# schematic.net
KiCad netlist of a schematic drawn in EAGLE
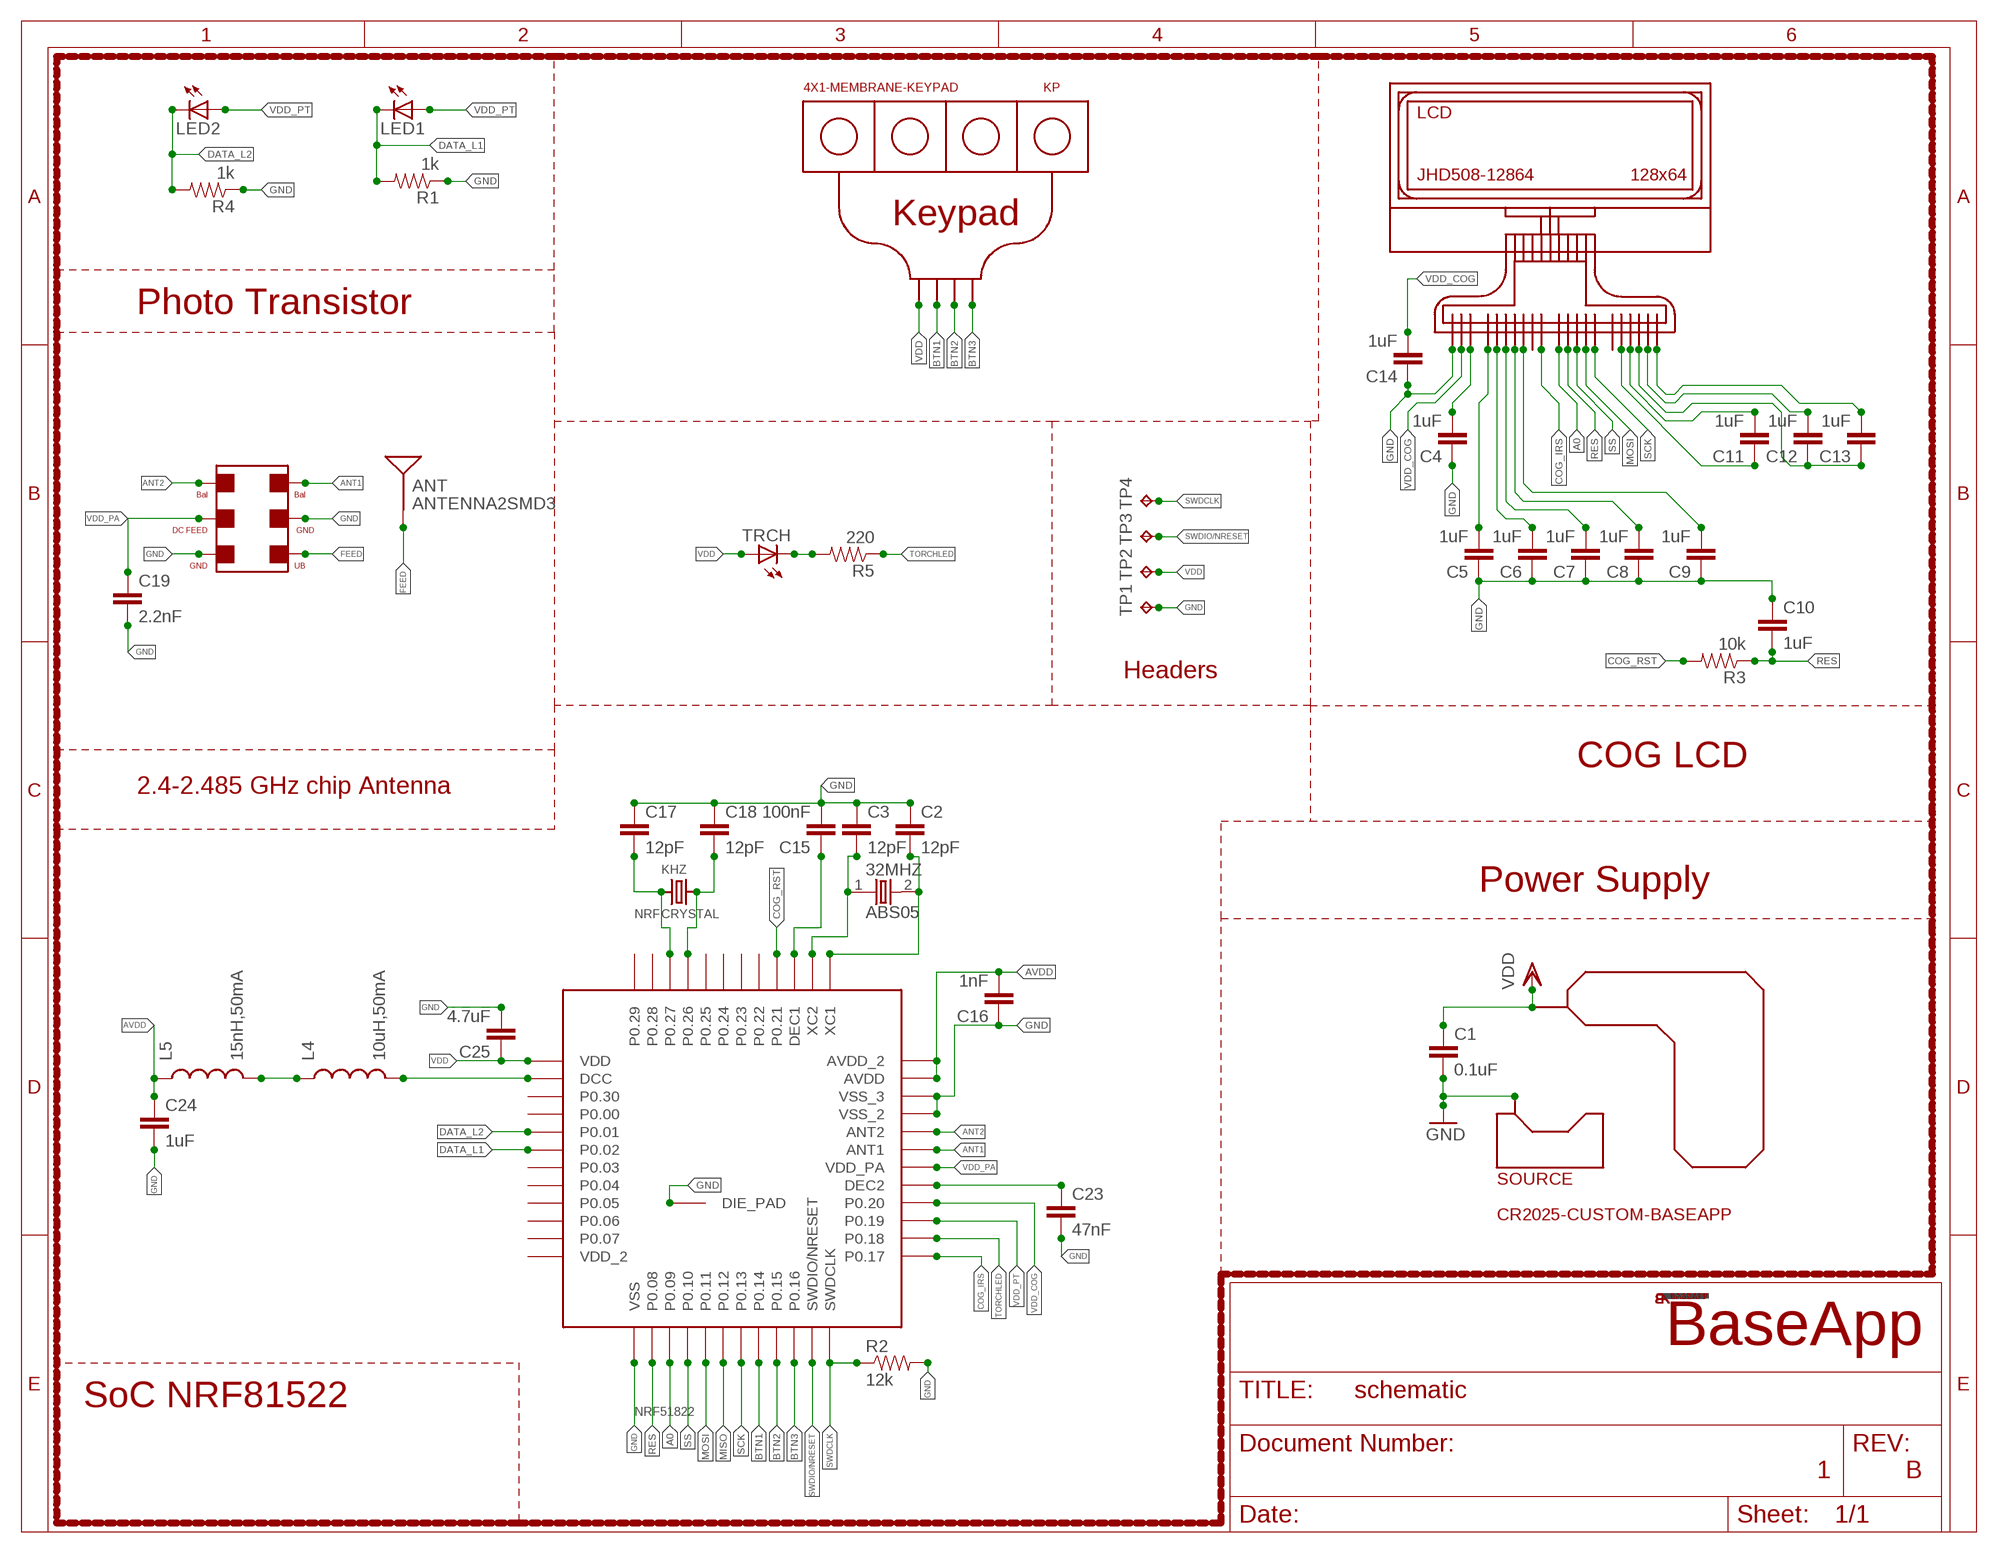
[diagram p0: schematic, sheet 1]

(export (version "E")
  (design (tool "Eeschema 10.0.6"))
  (components
    (comp (ref "32MHZ")
      (value "ABS05")
      (footprint "eagle-import:ABS05")
      (libsource (lib "eagle-import") (part "ABS05"))
    )
    (comp (ref "ANT")
      (value "ANTENNA2SMD3")
      (footprint "eagle-import:ANTENNA-CHIP4")
      (libsource (lib "eagle-import") (part "ANTENNA2SMD3"))
    )
    (comp (ref "BU")
      (value "2450BM14E0003_BALUN")
      (footprint "eagle-import:6PCPADS")
      (libsource (lib "eagle-import") (part "2450BM14E0003_BALUN"))
    )
    (comp (ref "C1")
      (value "0.1uF")
      (footprint "eagle-import:0402-CAP")
      (libsource (lib "eagle-import") (part "CAP0402-CAP"))
    )
    (comp (ref "C2")
      (value "12pF")
      (footprint "eagle-import:0402-CAP")
      (libsource (lib "eagle-import") (part "CAP0402-CAP"))
    )
    (comp (ref "C3")
      (value "12pF")
      (footprint "eagle-import:0402-CAP")
      (libsource (lib "eagle-import") (part "CAP0402-CAP"))
    )
    (comp (ref "C4")
      (value "1uF")
      (footprint "eagle-import:0402-CAP")
      (libsource (lib "eagle-import") (part "CAP0402-CAP"))
    )
    (comp (ref "C5")
      (value "1uF")
      (footprint "eagle-import:0402-CAP")
      (libsource (lib "eagle-import") (part "CAP0402-CAP"))
    )
    (comp (ref "C6")
      (value "1uF")
      (footprint "eagle-import:0402-CAP")
      (libsource (lib "eagle-import") (part "CAP0402-CAP"))
    )
    (comp (ref "C7")
      (value "1uF")
      (footprint "eagle-import:0402-CAP")
      (libsource (lib "eagle-import") (part "CAP0402-CAP"))
    )
    (comp (ref "C8")
      (value "1uF")
      (footprint "eagle-import:0402-CAP")
      (libsource (lib "eagle-import") (part "CAP0402-CAP"))
    )
    (comp (ref "C9")
      (value "1uF")
      (footprint "eagle-import:0402-CAP")
      (libsource (lib "eagle-import") (part "CAP0402-CAP"))
    )
    (comp (ref "C10")
      (value "1uF")
      (footprint "eagle-import:0402-CAP")
      (libsource (lib "eagle-import") (part "CAP0402-CAP"))
    )
    (comp (ref "C11")
      (value "1uF")
      (footprint "eagle-import:0402-CAP")
      (libsource (lib "eagle-import") (part "CAP0402-CAP"))
    )
    (comp (ref "C12")
      (value "1uF")
      (footprint "eagle-import:0402-CAP")
      (libsource (lib "eagle-import") (part "CAP0402-CAP"))
    )
    (comp (ref "C13")
      (value "1uF")
      (footprint "eagle-import:0402-CAP")
      (libsource (lib "eagle-import") (part "CAP0402-CAP"))
    )
    (comp (ref "C14")
      (value "1uF")
      (footprint "eagle-import:0402-CAP")
      (libsource (lib "eagle-import") (part "CAP0402-CAP"))
    )
    (comp (ref "C15")
      (value "100nF")
      (footprint "eagle-import:0402-CAP")
      (libsource (lib "eagle-import") (part "CAP0402-CAP"))
    )
    (comp (ref "C16")
      (value "1nF")
      (footprint "eagle-import:0402-CAP")
      (libsource (lib "eagle-import") (part "CAP0402-CAP"))
    )
    (comp (ref "C17")
      (value "12pF")
      (footprint "eagle-import:0402-CAP")
      (libsource (lib "eagle-import") (part "CAP0402-CAP"))
    )
    (comp (ref "C18")
      (value "12pF")
      (footprint "eagle-import:0402-CAP")
      (libsource (lib "eagle-import") (part "CAP0402-CAP"))
    )
    (comp (ref "C19")
      (value "2.2nF")
      (footprint "eagle-import:0402-CAP")
      (libsource (lib "eagle-import") (part "CAP0402-CAP"))
    )
    (comp (ref "C23")
      (value "47nF")
      (footprint "eagle-import:0402-CAP")
      (libsource (lib "eagle-import") (part "CAP0402-CAP"))
    )
    (comp (ref "C24")
      (value "1uF")
      (footprint "eagle-import:0402-CAP")
      (libsource (lib "eagle-import") (part "CAP0402-CAP"))
    )
    (comp (ref "C25")
      (value "4.7uF")
      (footprint "eagle-import:0402-CAP")
      (libsource (lib "eagle-import") (part "CAP0402-CAP"))
    )
    (comp (ref "KHZ")
      (value "CRYSTAL")
      (footprint "eagle-import:ABS05")
      (libsource (lib "eagle-import") (part "CRYSTAL"))
    )
    (comp (ref "KP")
      (value "4X1-MEMBRANE-KEYPAD")
      (footprint "eagle-import:4X1-MEMBRANE-KEYPAD")
      (libsource (lib "eagle-import") (part "4X1-MEMBRANE-KEYPAD"))
    )
    (comp (ref "L4")
      (value "10uH,50mA")
      (footprint "eagle-import:C0402")
      (libsource (lib "eagle-import") (part "INDUCTOR0402"))
    )
    (comp (ref "L5")
      (value "15nH,50mA")
      (footprint "eagle-import:C0402")
      (libsource (lib "eagle-import") (part "INDUCTOR0402"))
    )
    (comp (ref "LCD")
      (value "JHD508-12864")
      (footprint "eagle-import:FSTN")
      (libsource (lib "eagle-import") (part "JHD508-12864"))
    )
    (comp (ref "LED1")
      (value "LEDCHIP-LED0805")
      (footprint "eagle-import:CHIP-LED0805")
      (libsource (lib "eagle-import") (part "LEDCHIP-LED0805"))
    )
    (comp (ref "LED2")
      (value "LEDCHIP-LED0805")
      (footprint "eagle-import:CHIP-LED0805")
      (libsource (lib "eagle-import") (part "LEDCHIP-LED0805"))
    )
    (comp (ref "NRF")
      (value "NRF51822")
      (footprint "eagle-import:QFN48")
      (libsource (lib "eagle-import") (part "NRF51822"))
    )
    (comp (ref "R1")
      (value "1k")
      (footprint "eagle-import:0402-RES")
      (libsource (lib "eagle-import") (part "RESISTOR0402-RES"))
    )
    (comp (ref "R2")
      (value "12k")
      (footprint "eagle-import:0402-RES")
      (libsource (lib "eagle-import") (part "RESISTOR0402-RES"))
    )
    (comp (ref "R3")
      (value "10k")
      (footprint "eagle-import:0402-RES")
      (libsource (lib "eagle-import") (part "RESISTOR0402-RES"))
    )
    (comp (ref "R4")
      (value "1k")
      (footprint "eagle-import:0402-RES")
      (libsource (lib "eagle-import") (part "RESISTOR0402-RES"))
    )
    (comp (ref "R5")
      (value "220")
      (footprint "eagle-import:0402-RES")
      (libsource (lib "eagle-import") (part "RESISTOR0402-RES"))
    )
    (comp (ref "SOURCE")
      (value "CR2025-CUSTOM-BASEAPP")
      (footprint "eagle-import:CR2025-CUSTOM-BASEAPP")
      (libsource (lib "eagle-import") (part "CR2025-CUSTOM-BASEAPP"))
    )
    (comp (ref "TP1")
      (value "TPTP06SQ")
      (footprint "eagle-import:TP06SQ")
      (libsource (lib "eagle-import") (part "TPTP06SQ"))
    )
    (comp (ref "TP2")
      (value "TPTP06SQ")
      (footprint "eagle-import:TP06SQ")
      (libsource (lib "eagle-import") (part "TPTP06SQ"))
    )
    (comp (ref "TP3")
      (value "TPTP06SQ")
      (footprint "eagle-import:TP06SQ")
      (libsource (lib "eagle-import") (part "TPTP06SQ"))
    )
    (comp (ref "TP4")
      (value "TPTP06SQ")
      (footprint "eagle-import:TP06SQ")
      (libsource (lib "eagle-import") (part "TPTP06SQ"))
    )
    (comp (ref "TRCH")
      (value "LEDSML0603")
      (footprint "eagle-import:SML0603")
      (libsource (lib "eagle-import") (part "LEDSML0603"))
    )
  )
  (nets
    (net (code "1") (name "A0") (class "Default")
      (node (ref "LCD") (pin "P$19") (pinfunction "A0_P$19") (pintype "bidirectional"))
      (node (ref "NRF") (pin "15") (pinfunction "P0.09_15") (pintype "bidirectional"))
    )
    (net (code "2") (name "ANT1") (class "Default")
      (node (ref "BU") (pin "P$3") (pinfunction "3_P$3") (pintype "bidirectional"))
      (node (ref "NRF") (pin "31") (pinfunction "ANT1_31") (pintype "bidirectional"))
    )
    (net (code "3") (name "ANT2") (class "Default")
      (node (ref "BU") (pin "P$4") (pinfunction "4_P$4") (pintype "bidirectional"))
      (node (ref "NRF") (pin "32") (pinfunction "ANT2_32") (pintype "bidirectional"))
    )
    (net (code "4") (name "AVDD") (class "Default")
      (node (ref "C16") (pin "2") (pinfunction "2_2") (pintype "passive"))
      (node (ref "C24") (pin "1") (pinfunction "1_1") (pintype "passive"))
      (node (ref "L5") (pin "1") (pinfunction "1_1") (pintype "passive"))
      (node (ref "NRF") (pin "35") (pinfunction "AVDD_35") (pintype "bidirectional"))
      (node (ref "NRF") (pin "36") (pinfunction "AVDD_2_36") (pintype "bidirectional"))
    )
    (net (code "5") (name "BTN1") (class "Default")
      (node (ref "KP") (pin "P$2") (pinfunction "P$2_P$2") (pintype "bidirectional"))
      (node (ref "NRF") (pin "20") (pinfunction "P0.14_20") (pintype "bidirectional"))
    )
    (net (code "6") (name "BTN2") (class "Default")
      (node (ref "KP") (pin "P$3") (pinfunction "P$3_P$3") (pintype "bidirectional"))
      (node (ref "NRF") (pin "21") (pinfunction "P0.15_21") (pintype "bidirectional"))
    )
    (net (code "7") (name "BTN3") (class "Default")
      (node (ref "KP") (pin "P$4") (pinfunction "P$4_P$4") (pintype "bidirectional"))
      (node (ref "NRF") (pin "22") (pinfunction "P0.16_22") (pintype "bidirectional"))
    )
    (net (code "8") (name "COG_IRS") (class "Default")
      (node (ref "LCD") (pin "P$1") (pinfunction "IRS_P$1") (pintype "bidirectional"))
      (node (ref "NRF") (pin "25") (pinfunction "P0.17_25") (pintype "bidirectional"))
    )
    (net (code "9") (name "COG_RST") (class "Default")
      (node (ref "NRF") (pin "40") (pinfunction "P0.21_40") (pintype "bidirectional"))
      (node (ref "R3") (pin "2") (pinfunction "2_2") (pintype "passive"))
    )
    (net (code "10") (name "DATA_L1") (class "Default")
      (node (ref "LED1") (pin "C") (pinfunction "C_C") (pintype "passive"))
      (node (ref "NRF") (pin "6") (pinfunction "P0.02_6") (pintype "bidirectional"))
      (node (ref "R1") (pin "2") (pinfunction "2_2") (pintype "passive"))
    )
    (net (code "11") (name "DATA_L2") (class "Default")
      (node (ref "LED2") (pin "C") (pinfunction "C_C") (pintype "passive"))
      (node (ref "NRF") (pin "5") (pinfunction "P0.01_5") (pintype "bidirectional"))
      (node (ref "R4") (pin "2") (pinfunction "2_2") (pintype "passive"))
    )
    (net (code "12") (name "FEED") (class "Default")
      (node (ref "ANT") (pin "SIG") (pinfunction "SIGNAL_SIG") (pintype "bidirectional"))
      (node (ref "BU") (pin "P$1") (pinfunction "1_P$1") (pintype "bidirectional"))
    )
    (net (code "13") (name "GND") (class "Default")
      (node (ref "BU") (pin "P$2") (pinfunction "2_P$2") (pintype "bidirectional"))
      (node (ref "BU") (pin "P$6") (pinfunction "6_P$6") (pintype "bidirectional"))
      (node (ref "C1") (pin "2") (pinfunction "2_2") (pintype "passive"))
      (node (ref "C10") (pin "1") (pinfunction "1_1") (pintype "passive"))
      (node (ref "C14") (pin "1") (pinfunction "1_1") (pintype "passive"))
      (node (ref "C15") (pin "2") (pinfunction "2_2") (pintype "passive"))
      (node (ref "C16") (pin "1") (pinfunction "1_1") (pintype "passive"))
      (node (ref "C17") (pin "1") (pinfunction "1_1") (pintype "passive"))
      (node (ref "C18") (pin "1") (pinfunction "1_1") (pintype "passive"))
      (node (ref "C19") (pin "2") (pinfunction "2_2") (pintype "passive"))
      (node (ref "C2") (pin "1") (pinfunction "1_1") (pintype "passive"))
      (node (ref "C23") (pin "2") (pinfunction "2_2") (pintype "passive"))
      (node (ref "C24") (pin "2") (pinfunction "2_2") (pintype "passive"))
      (node (ref "C25") (pin "2") (pinfunction "2_2") (pintype "passive"))
      (node (ref "C3") (pin "1") (pinfunction "1_1") (pintype "passive"))
      (node (ref "C4") (pin "1") (pinfunction "1_1") (pintype "passive"))
      (node (ref "C5") (pin "1") (pinfunction "1_1") (pintype "passive"))
      (node (ref "C6") (pin "1") (pinfunction "1_1") (pintype "passive"))
      (node (ref "C7") (pin "1") (pinfunction "1_1") (pintype "passive"))
      (node (ref "C8") (pin "1") (pinfunction "1_1") (pintype "passive"))
      (node (ref "C9") (pin "1") (pinfunction "1_1") (pintype "passive"))
      (node (ref "LCD") (pin "P$15") (pinfunction "GND_P$15") (pintype "bidirectional"))
      (node (ref "NRF") (pin "13") (pinfunction "VSS_13") (pintype "bidirectional"))
      (node (ref "NRF") (pin "33") (pinfunction "VSS_2_33") (pintype "bidirectional"))
      (node (ref "NRF") (pin "34") (pinfunction "VSS_3_34") (pintype "bidirectional"))
      (node (ref "NRF") (pin "GND") (pinfunction "DIE_PAD_GND") (pintype "bidirectional"))
      (node (ref "R1") (pin "1") (pinfunction "1_1") (pintype "passive"))
      (node (ref "R2") (pin "2") (pinfunction "2_2") (pintype "passive"))
      (node (ref "R4") (pin "1") (pinfunction "1_1") (pintype "passive"))
      (node (ref "SOURCE") (pin "1") (pinfunction "GND_1") (pintype "bidirectional"))
      (node (ref "TP1") (pin "TP") (pinfunction "TP_TP") (pintype "input"))
    )
    (net (code "14") (name "MISO") (class "Default")
      (node (ref "NRF") (pin "18") (pinfunction "P0.12_18") (pintype "bidirectional"))
    )
    (net (code "15") (name "MOSI") (class "Default")
      (node (ref "LCD") (pin "P$17") (pinfunction "SI_P$17") (pintype "bidirectional"))
      (node (ref "NRF") (pin "17") (pinfunction "P0.11_17") (pintype "bidirectional"))
    )
    (net (code "16") (name "Net-(KHZ-1)") (class "Default")
      (node (ref "C17") (pin "2") (pinfunction "2_2") (pintype "passive"))
      (node (ref "KHZ") (pin "P$1") (pinfunction "1_P$1") (pintype "passive"))
      (node (ref "NRF") (pin "46") (pinfunction "P0.27_46") (pintype "bidirectional"))
    )
    (net (code "17") (name "Net-(KHZ-2)") (class "Default")
      (node (ref "C18") (pin "2") (pinfunction "2_2") (pintype "passive"))
      (node (ref "KHZ") (pin "P$2") (pinfunction "2_P$2") (pintype "passive"))
      (node (ref "NRF") (pin "45") (pinfunction "P0.26_45") (pintype "bidirectional"))
    )
    (net (code "18") (name "Net-(L4-Pad1)") (class "Default")
      (node (ref "L4") (pin "1") (pinfunction "1_1") (pintype "passive"))
      (node (ref "L5") (pin "2") (pinfunction "2_2") (pintype "passive"))
    )
    (net (code "19") (name "Net-(LCD-CAP1N)") (class "Default")
      (node (ref "C12") (pin "1") (pinfunction "1_1") (pintype "passive"))
      (node (ref "C13") (pin "1") (pinfunction "1_1") (pintype "passive"))
      (node (ref "LCD") (pin "P$11") (pinfunction "CAP1N_P$11") (pintype "bidirectional"))
    )
    (net (code "20") (name "Net-(LCD-CAP1P)") (class "Default")
      (node (ref "C12") (pin "2") (pinfunction "2_2") (pintype "passive"))
      (node (ref "LCD") (pin "P$12") (pinfunction "CAP1P_P$12") (pintype "bidirectional"))
    )
    (net (code "21") (name "Net-(LCD-CAP2N)") (class "Default")
      (node (ref "C11") (pin "2") (pinfunction "2_2") (pintype "passive"))
      (node (ref "LCD") (pin "P$10") (pinfunction "CAP2N_P$10") (pintype "bidirectional"))
    )
    (net (code "22") (name "Net-(LCD-CAP2P)") (class "Default")
      (node (ref "C11") (pin "1") (pinfunction "1_1") (pintype "passive"))
      (node (ref "LCD") (pin "P$9") (pinfunction "CAP2P_P$9") (pintype "bidirectional"))
    )
    (net (code "23") (name "Net-(LCD-CAP3N)") (class "Default")
      (node (ref "C13") (pin "2") (pinfunction "2_2") (pintype "passive"))
      (node (ref "LCD") (pin "P$13") (pinfunction "CAP3N_P$13") (pintype "bidirectional"))
    )
    (net (code "24") (name "Net-(LCD-V1)") (class "Default")
      (node (ref "C5") (pin "2") (pinfunction "2_2") (pintype "passive"))
      (node (ref "LCD") (pin "P$7") (pinfunction "V1_P$7") (pintype "bidirectional"))
    )
    (net (code "25") (name "Net-(LCD-V2)") (class "Default")
      (node (ref "C6") (pin "2") (pinfunction "2_2") (pintype "passive"))
      (node (ref "LCD") (pin "P$6") (pinfunction "V2_P$6") (pintype "bidirectional"))
    )
    (net (code "26") (name "Net-(LCD-V3)") (class "Default")
      (node (ref "C7") (pin "2") (pinfunction "2_2") (pintype "passive"))
      (node (ref "LCD") (pin "P$5") (pinfunction "V3_P$5") (pintype "bidirectional"))
    )
    (net (code "27") (name "Net-(LCD-V4)") (class "Default")
      (node (ref "C8") (pin "2") (pinfunction "2_2") (pintype "passive"))
      (node (ref "LCD") (pin "P$4") (pinfunction "V4_P$4") (pintype "bidirectional"))
    )
    (net (code "28") (name "Net-(LCD-V5)") (class "Default")
      (node (ref "C9") (pin "2") (pinfunction "2_2") (pintype "passive"))
      (node (ref "LCD") (pin "P$3") (pinfunction "V5_P$3") (pintype "bidirectional"))
    )
    (net (code "29") (name "Net-(LCD-VOUT)") (class "Default")
      (node (ref "C4") (pin "2") (pinfunction "2_2") (pintype "passive"))
      (node (ref "LCD") (pin "P$14") (pinfunction "VOUT_P$14") (pintype "bidirectional"))
    )
    (net (code "30") (name "Net-(NRF-DCC)") (class "Default")
      (node (ref "L4") (pin "2") (pinfunction "2_2") (pintype "passive"))
      (node (ref "NRF") (pin "2") (pinfunction "DCC_2") (pintype "bidirectional"))
    )
    (net (code "31") (name "Net-(NRF-DEC1)") (class "Default")
      (node (ref "C15") (pin "1") (pinfunction "1_1") (pintype "passive"))
      (node (ref "NRF") (pin "39") (pinfunction "DEC1_39") (pintype "bidirectional"))
    )
    (net (code "32") (name "Net-(NRF-DEC2)") (class "Default")
      (node (ref "C23") (pin "1") (pinfunction "1_1") (pintype "passive"))
      (node (ref "NRF") (pin "29") (pinfunction "DEC2_29") (pintype "bidirectional"))
    )
    (net (code "33") (name "Net-(NRF-XC1)") (class "Default")
      (node (ref "32MHZ") (pin "2") (pinfunction "2_2") (pintype "passive"))
      (node (ref "C2") (pin "2") (pinfunction "2_2") (pintype "passive"))
      (node (ref "NRF") (pin "37") (pinfunction "XC1_37") (pintype "bidirectional"))
    )
    (net (code "34") (name "Net-(NRF-XC2)") (class "Default")
      (node (ref "32MHZ") (pin "1") (pinfunction "1_1") (pintype "passive"))
      (node (ref "C3") (pin "2") (pinfunction "2_2") (pintype "passive"))
      (node (ref "NRF") (pin "38") (pinfunction "XC2_38") (pintype "bidirectional"))
    )
    (net (code "35") (name "Net-(R5-Pad2)") (class "Default")
      (node (ref "R5") (pin "2") (pinfunction "2_2") (pintype "passive"))
      (node (ref "TRCH") (pin "C") (pinfunction "C_C") (pintype "passive"))
    )
    (net (code "36") (name "RES") (class "Default")
      (node (ref "C10") (pin "2") (pinfunction "2_2") (pintype "passive"))
      (node (ref "LCD") (pin "P$20") (pinfunction "/RES_P$20") (pintype "bidirectional"))
      (node (ref "NRF") (pin "14") (pinfunction "P0.08_14") (pintype "bidirectional"))
      (node (ref "R3") (pin "1") (pinfunction "1_1") (pintype "passive"))
    )
    (net (code "37") (name "SCK") (class "Default")
      (node (ref "LCD") (pin "P$18") (pinfunction "SCL_P$18") (pintype "bidirectional"))
      (node (ref "NRF") (pin "19") (pinfunction "P0.13_19") (pintype "bidirectional"))
    )
    (net (code "38") (name "SS") (class "Default")
      (node (ref "LCD") (pin "P$21") (pinfunction "/CS1_P$21") (pintype "bidirectional"))
      (node (ref "NRF") (pin "16") (pinfunction "P0.10_16") (pintype "bidirectional"))
    )
    (net (code "39") (name "SWDCLK") (class "Default")
      (node (ref "NRF") (pin "24") (pinfunction "SWDCLK_24") (pintype "bidirectional"))
      (node (ref "R2") (pin "1") (pinfunction "1_1") (pintype "passive"))
      (node (ref "TP4") (pin "TP") (pinfunction "TP_TP") (pintype "input"))
    )
    (net (code "40") (name "SWDIO{slash}NRESET") (class "Default")
      (node (ref "NRF") (pin "23") (pinfunction "SWDIO/NRESET_23") (pintype "bidirectional"))
      (node (ref "TP3") (pin "TP") (pinfunction "TP_TP") (pintype "input"))
    )
    (net (code "41") (name "TORCHLED") (class "Default")
      (node (ref "NRF") (pin "26") (pinfunction "P0.18_26") (pintype "bidirectional"))
      (node (ref "R5") (pin "1") (pinfunction "1_1") (pintype "passive"))
    )
    (net (code "42") (name "VDD") (class "Default")
      (node (ref "C1") (pin "1") (pinfunction "1_1") (pintype "passive"))
      (node (ref "C25") (pin "1") (pinfunction "1_1") (pintype "passive"))
      (node (ref "KP") (pin "P$1") (pinfunction "P$1_P$1") (pintype "bidirectional"))
      (node (ref "NRF") (pin "1") (pinfunction "VDD_1") (pintype "bidirectional"))
      (node (ref "SOURCE") (pin "2") (pinfunction "VDD_2") (pintype "bidirectional"))
      (node (ref "TP2") (pin "TP") (pinfunction "TP_TP") (pintype "input"))
      (node (ref "TRCH") (pin "A") (pinfunction "A_A") (pintype "passive"))
    )
    (net (code "43") (name "VDD_COG") (class "Default")
      (node (ref "C14") (pin "2") (pinfunction "2_2") (pintype "passive"))
      (node (ref "LCD") (pin "P$16") (pinfunction "VDD_P$16") (pintype "bidirectional"))
      (node (ref "NRF") (pin "28") (pinfunction "P0.20_28") (pintype "bidirectional"))
    )
    (net (code "44") (name "VDD_PA") (class "Default")
      (node (ref "BU") (pin "P$5") (pinfunction "5_P$5") (pintype "bidirectional"))
      (node (ref "C19") (pin "1") (pinfunction "1_1") (pintype "passive"))
      (node (ref "NRF") (pin "30") (pinfunction "VDD_PA_30") (pintype "bidirectional"))
    )
    (net (code "45") (name "VDD_PT") (class "Default")
      (node (ref "LED1") (pin "A") (pinfunction "A_A") (pintype "passive"))
      (node (ref "LED2") (pin "A") (pinfunction "A_A") (pintype "passive"))
      (node (ref "NRF") (pin "27") (pinfunction "P0.19_27") (pintype "bidirectional"))
    )
    (net (code "46") (name "unconnected-(LCD-CAP4N-PadP$8)") (class "Default")
      (node (ref "LCD") (pin "P$8") (pinfunction "CAP4N_P$8") (pintype "bidirectional"))
    )
    (net (code "47") (name "unconnected-(LCD-VR-PadP$2)") (class "Default")
      (node (ref "LCD") (pin "P$2") (pinfunction "VR_P$2") (pintype "bidirectional"))
    )
    (net (code "48") (name "unconnected-(NRF-P0.00-Pad4)") (class "Default")
      (node (ref "NRF") (pin "4") (pinfunction "P0.00_4") (pintype "bidirectional"))
    )
    (net (code "49") (name "unconnected-(NRF-P0.03-Pad7)") (class "Default")
      (node (ref "NRF") (pin "7") (pinfunction "P0.03_7") (pintype "bidirectional"))
    )
    (net (code "50") (name "unconnected-(NRF-P0.04-Pad8)") (class "Default")
      (node (ref "NRF") (pin "8") (pinfunction "P0.04_8") (pintype "bidirectional"))
    )
    (net (code "51") (name "unconnected-(NRF-P0.05-Pad9)") (class "Default")
      (node (ref "NRF") (pin "9") (pinfunction "P0.05_9") (pintype "bidirectional"))
    )
    (net (code "52") (name "unconnected-(NRF-P0.06-Pad10)") (class "Default")
      (node (ref "NRF") (pin "10") (pinfunction "P0.06_10") (pintype "bidirectional"))
    )
    (net (code "53") (name "unconnected-(NRF-P0.07-Pad11)") (class "Default")
      (node (ref "NRF") (pin "11") (pinfunction "P0.07_11") (pintype "bidirectional"))
    )
    (net (code "54") (name "unconnected-(NRF-P0.22-Pad41)") (class "Default")
      (node (ref "NRF") (pin "41") (pinfunction "P0.22_41") (pintype "bidirectional"))
    )
    (net (code "55") (name "unconnected-(NRF-P0.23-Pad42)") (class "Default")
      (node (ref "NRF") (pin "42") (pinfunction "P0.23_42") (pintype "bidirectional"))
    )
    (net (code "56") (name "unconnected-(NRF-P0.24-Pad43)") (class "Default")
      (node (ref "NRF") (pin "43") (pinfunction "P0.24_43") (pintype "bidirectional"))
    )
    (net (code "57") (name "unconnected-(NRF-P0.25-Pad44)") (class "Default")
      (node (ref "NRF") (pin "44") (pinfunction "P0.25_44") (pintype "bidirectional"))
    )
    (net (code "58") (name "unconnected-(NRF-P0.28-Pad47)") (class "Default")
      (node (ref "NRF") (pin "47") (pinfunction "P0.28_47") (pintype "bidirectional"))
    )
    (net (code "59") (name "unconnected-(NRF-P0.29-Pad48)") (class "Default")
      (node (ref "NRF") (pin "48") (pinfunction "P0.29_48") (pintype "bidirectional"))
    )
    (net (code "60") (name "unconnected-(NRF-P0.30-Pad3)") (class "Default")
      (node (ref "NRF") (pin "3") (pinfunction "P0.30_3") (pintype "bidirectional"))
    )
    (net (code "61") (name "unconnected-(NRF-VDD_2-Pad12)") (class "Default")
      (node (ref "NRF") (pin "12") (pinfunction "VDD_2_12") (pintype "bidirectional"))
    )
  )
)
